# linea_base.net
KiCad netlist of a schematic drawn in EAGLE
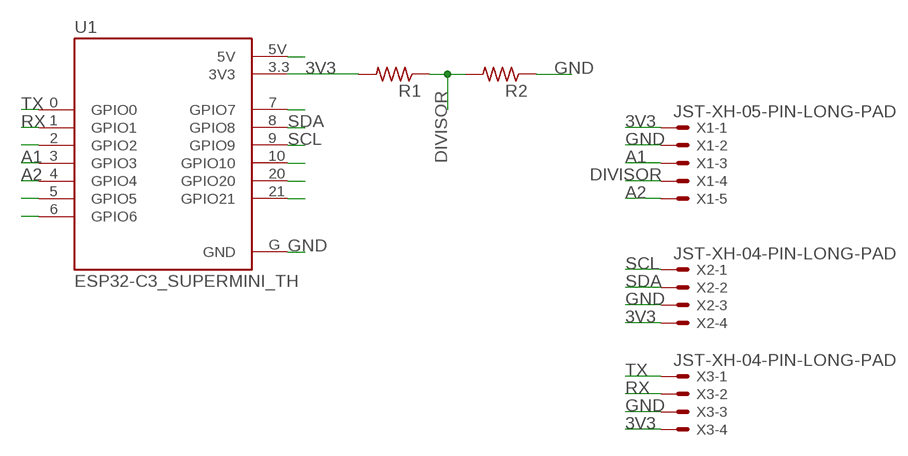
[diagram p0: schematic, sheet 1]

(export (version "E")
  (design (tool "Eeschema 10.0.6"))
  (components
    (comp (ref "R1")
      (value "R-US_0204/7")
      (footprint "eagle-import:0204_7")
      (libsource (lib "eagle-import") (part "R-US_0204/7"))
    )
    (comp (ref "R2")
      (value "R-US_0204/7")
      (footprint "eagle-import:0204_7")
      (libsource (lib "eagle-import") (part "R-US_0204/7"))
    )
    (comp (ref "U1")
      (value "ESP32-C3_SUPERMINI_TH")
      (footprint "eagle-import:MODULE_ESP32-C3_SUPERMINI_TH")
      (fields (field (name "MF") "Espressif Systems") (field (name "MP") "ESP32-C3 SuperMini_TH"))
      (libsource (lib "eagle-import") (part "ESP32-C3_SUPERMINI_TH"))
    )
    (comp (ref "X1")
      (value "JST-XH-05-PIN-LONG-PAD")
      (footprint "eagle-import:JST-XH-05-PACKAGE-LONG-PAD")
      (libsource (lib "eagle-import") (part "JST-XH-05-PIN-LONG-PAD"))
    )
    (comp (ref "X2")
      (value "JST-XH-04-PIN-LONG-PAD")
      (footprint "eagle-import:JST-XH-04-PACKAGE-LONG-PAD")
      (libsource (lib "eagle-import") (part "JST-XH-04-PIN-LONG-PAD"))
    )
    (comp (ref "X3")
      (value "JST-XH-04-PIN-LONG-PAD")
      (footprint "eagle-import:JST-XH-04-PACKAGE-LONG-PAD")
      (libsource (lib "eagle-import") (part "JST-XH-04-PIN-LONG-PAD"))
    )
  )
  (nets
    (net (code "1") (name "/3V3") (class "Default")
      (node (ref "R1") (pin "2") (pinfunction "2_2") (pintype "passive"))
      (node (ref "U1") (pin "3.3") (pinfunction "3V3_3.3") (pintype "power_in"))
      (node (ref "X1") (pin "1") (pinfunction "S_1") (pintype "passive"))
      (node (ref "X2") (pin "4") (pinfunction "S_4") (pintype "passive"))
      (node (ref "X3") (pin "4") (pinfunction "S_4") (pintype "passive"))
    )
    (net (code "2") (name "/A1") (class "Default")
      (node (ref "U1") (pin "3") (pinfunction "GPIO3_3") (pintype "bidirectional"))
      (node (ref "X1") (pin "3") (pinfunction "S_3") (pintype "passive"))
    )
    (net (code "3") (name "/A2") (class "Default")
      (node (ref "U1") (pin "4") (pinfunction "GPIO4_4") (pintype "bidirectional"))
      (node (ref "X1") (pin "5") (pinfunction "S_5") (pintype "passive"))
    )
    (net (code "4") (name "/DIVISOR") (class "Default")
      (node (ref "R1") (pin "1") (pinfunction "1_1") (pintype "passive"))
      (node (ref "R2") (pin "2") (pinfunction "2_2") (pintype "passive"))
      (node (ref "X1") (pin "4") (pinfunction "S_4") (pintype "passive"))
    )
    (net (code "5") (name "/GND") (class "Default")
      (node (ref "R2") (pin "1") (pinfunction "1_1") (pintype "passive"))
      (node (ref "U1") (pin "G") (pinfunction "GND_G") (pintype "power_in"))
      (node (ref "X1") (pin "2") (pinfunction "S_2") (pintype "passive"))
      (node (ref "X2") (pin "3") (pinfunction "S_3") (pintype "passive"))
      (node (ref "X3") (pin "3") (pinfunction "S_3") (pintype "passive"))
    )
    (net (code "6") (name "/RX") (class "Default")
      (node (ref "U1") (pin "1") (pinfunction "GPIO1_1") (pintype "bidirectional"))
      (node (ref "X3") (pin "2") (pinfunction "S_2") (pintype "passive"))
    )
    (net (code "7") (name "/SCL") (class "Default")
      (node (ref "U1") (pin "9") (pinfunction "GPIO9_9") (pintype "bidirectional"))
      (node (ref "X2") (pin "1") (pinfunction "S_1") (pintype "passive"))
    )
    (net (code "8") (name "/SDA") (class "Default")
      (node (ref "U1") (pin "8") (pinfunction "GPIO8_8") (pintype "bidirectional"))
      (node (ref "X2") (pin "2") (pinfunction "S_2") (pintype "passive"))
    )
    (net (code "9") (name "/TX") (class "Default")
      (node (ref "U1") (pin "0") (pinfunction "GPIO0_0") (pintype "bidirectional"))
      (node (ref "X3") (pin "1") (pinfunction "S_1") (pintype "passive"))
    )
    (net (code "10") (name "unconnected-(U1-GPIO2-Pad2)") (class "Default")
      (node (ref "U1") (pin "2") (pinfunction "GPIO2_2") (pintype "bidirectional"))
    )
    (net (code "11") (name "unconnected-(U1-GPIO5-Pad5)") (class "Default")
      (node (ref "U1") (pin "5") (pinfunction "GPIO5_5") (pintype "bidirectional"))
    )
    (net (code "12") (name "unconnected-(U1-GPIO6-Pad6)") (class "Default")
      (node (ref "U1") (pin "6") (pinfunction "GPIO6_6") (pintype "bidirectional"))
    )
    (net (code "13") (name "unconnected-(U1-GPIO7-Pad7)") (class "Default")
      (node (ref "U1") (pin "7") (pinfunction "GPIO7_7") (pintype "bidirectional"))
    )
    (net (code "14") (name "unconnected-(U1-GPIO10-Pad10)") (class "Default")
      (node (ref "U1") (pin "10") (pinfunction "GPIO10_10") (pintype "bidirectional"))
    )
    (net (code "15") (name "unconnected-(U1-GPIO20-Pad20)") (class "Default")
      (node (ref "U1") (pin "20") (pinfunction "GPIO20_20") (pintype "bidirectional"))
    )
    (net (code "16") (name "unconnected-(U1-GPIO21-Pad21)") (class "Default")
      (node (ref "U1") (pin "21") (pinfunction "GPIO21_21") (pintype "bidirectional"))
    )
    (net (code "17") (name "unconnected-(U1-Pad5V)") (class "Default")
      (node (ref "U1") (pin "5V") (pinfunction "5V_5V") (pintype "power_in"))
    )
  )
)
